# 2014_CANSAT_Power_Supply.net
KiCad netlist of a schematic drawn in EAGLE
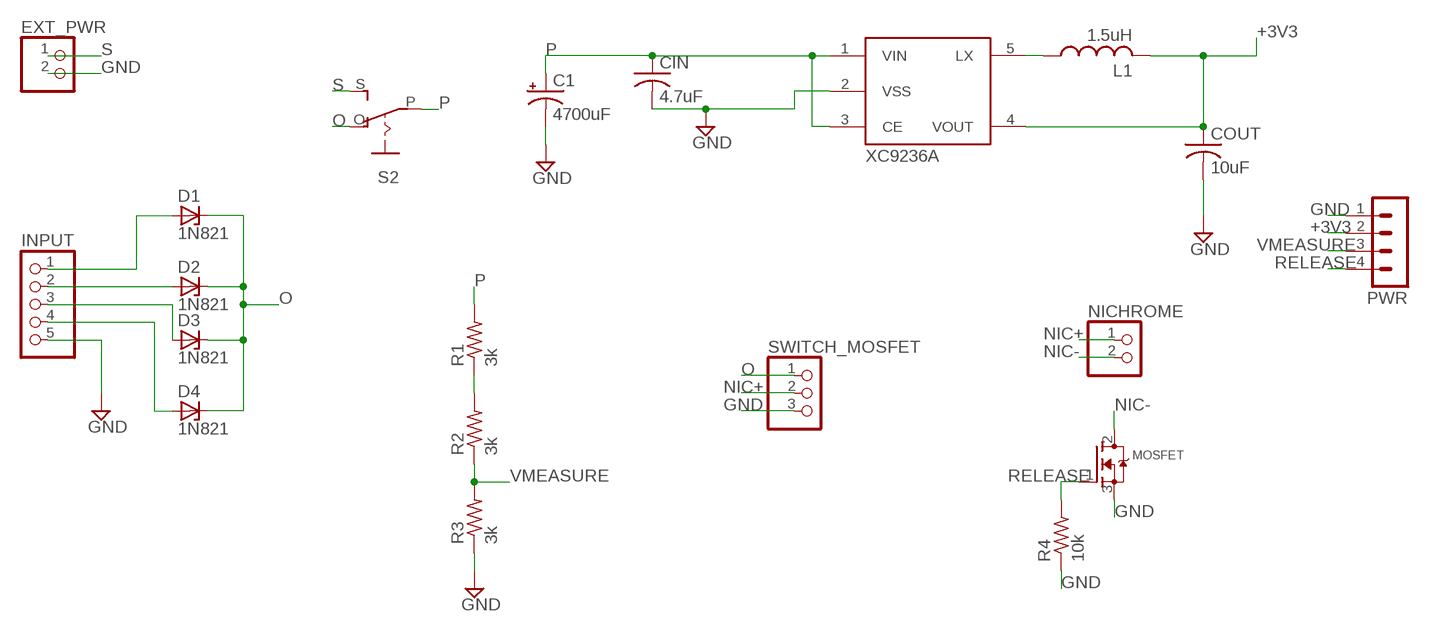
[diagram p0: schematic, sheet 1]

(export (version "E")
  (design (tool "Eeschema 10.0.6"))
  (components
    (comp (ref "C1")
      (value "4700uF")
      (footprint "eagle-import:E5-5")
      (libsource (lib "eagle-import") (part "CPOL-USE5-5"))
    )
    (comp (ref "CIN")
      (value "4.7uF")
      (footprint "eagle-import:C050-024X044")
      (libsource (lib "eagle-import") (part "C-US050-024X044"))
    )
    (comp (ref "COUT")
      (value "10uF")
      (footprint "eagle-import:C050-024X044")
      (libsource (lib "eagle-import") (part "C-US050-024X044"))
    )
    (comp (ref "D1")
      (value "1N821")
      (footprint "eagle-import:DO35Z10")
      (libsource (lib "eagle-import") (part "1N821"))
    )
    (comp (ref "D2")
      (value "1N821")
      (footprint "eagle-import:DO35Z10")
      (libsource (lib "eagle-import") (part "1N821"))
    )
    (comp (ref "D3")
      (value "1N821")
      (footprint "eagle-import:DO35Z10")
      (libsource (lib "eagle-import") (part "1N821"))
    )
    (comp (ref "D4")
      (value "1N821")
      (footprint "eagle-import:DO35Z10")
      (libsource (lib "eagle-import") (part "1N821"))
    )
    (comp (ref "EXT_PWR")
      (value "PINHD-1X2")
      (footprint "eagle-import:1X02")
      (libsource (lib "eagle-import") (part "PINHD-1X2"))
    )
    (comp (ref "INPUT")
      (value "PINHD-1X5")
      (footprint "eagle-import:1X05")
      (libsource (lib "eagle-import") (part "PINHD-1X5"))
    )
    (comp (ref "L1")
      (value "1.5uH")
      (footprint "eagle-import:6000-XXXX-RC")
      (libsource (lib "eagle-import") (part "L-US6000-XXX-RC"))
    )
    (comp (ref "MOSFET")
      (value "MOSFET-NGDS_TO220V")
      (footprint "eagle-import:TO220V")
      (libsource (lib "eagle-import") (part "MOSFET-NGDS_TO220V"))
    )
    (comp (ref "NICHROME")
      (value "PINHD-1X2")
      (footprint "eagle-import:1X02")
      (libsource (lib "eagle-import") (part "PINHD-1X2"))
    )
    (comp (ref "PWR")
      (value "MA04-1")
      (footprint "eagle-import:MA04-1")
      (libsource (lib "eagle-import") (part "MA04-1"))
    )
    (comp (ref "R1")
      (value "3k")
      (footprint "eagle-import:0309_10")
      (libsource (lib "eagle-import") (part "R-US_0309/10"))
    )
    (comp (ref "R2")
      (value "3k")
      (footprint "eagle-import:0309_10")
      (libsource (lib "eagle-import") (part "R-US_0309/10"))
    )
    (comp (ref "R3")
      (value "3k")
      (footprint "eagle-import:0309_10")
      (libsource (lib "eagle-import") (part "R-US_0309/10"))
    )
    (comp (ref "R4")
      (value "10k")
      (footprint "eagle-import:0309_10")
      (libsource (lib "eagle-import") (part "R-US_0309/10"))
    )
    (comp (ref "S2")
      (value "EG1218S")
      (footprint "eagle-import:EG1218")
      (libsource (lib "eagle-import") (part "EG1218S"))
    )
    (comp (ref "SWITCH_MOSFET")
      (value "PINHD-1X3")
      (footprint "eagle-import:1X03")
      (libsource (lib "eagle-import") (part "PINHD-1X3"))
    )
    (comp (ref "XC9236A")
      (value "MCP73811/2")
      (footprint "eagle-import:SOT23-5L")
      (libsource (lib "eagle-import") (part "MCP73811/2"))
    )
  )
  (nets
    (net (code "1") (name "/+3V3") (class "Default")
      (node (ref "COUT") (pin "1") (pinfunction "1_1") (pintype "passive"))
      (node (ref "L1") (pin "2") (pinfunction "2_2") (pintype "passive"))
      (node (ref "PWR") (pin "2") (pinfunction "2_2") (pintype "passive"))
      (node (ref "XC9236A") (pin "4") (pinfunction "VOUT_4") (pintype "power_in"))
    )
    (net (code "2") (name "/NIC+") (class "Default")
      (node (ref "NICHROME") (pin "1") (pinfunction "1_1") (pintype "passive"))
      (node (ref "SWITCH_MOSFET") (pin "2") (pinfunction "2_2") (pintype "passive"))
    )
    (net (code "3") (name "/NIC-") (class "Default")
      (node (ref "MOSFET") (pin "2") (pinfunction "D_2") (pintype "bidirectional"))
      (node (ref "NICHROME") (pin "2") (pinfunction "2_2") (pintype "passive"))
    )
    (net (code "4") (name "/O") (class "Default")
      (node (ref "D1") (pin "C") (pinfunction "C_C") (pintype "passive"))
      (node (ref "D2") (pin "C") (pinfunction "C_C") (pintype "passive"))
      (node (ref "D3") (pin "C") (pinfunction "C_C") (pintype "passive"))
      (node (ref "D4") (pin "C") (pinfunction "C_C") (pintype "passive"))
      (node (ref "S2") (pin "O") (pinfunction "O_O") (pintype "passive"))
      (node (ref "SWITCH_MOSFET") (pin "1") (pinfunction "1_1") (pintype "passive"))
    )
    (net (code "5") (name "/P") (class "Default")
      (node (ref "C1") (pin "+") (pinfunction "+_+") (pintype "passive"))
      (node (ref "CIN") (pin "1") (pinfunction "1_1") (pintype "passive"))
      (node (ref "R1") (pin "2") (pinfunction "2_2") (pintype "passive"))
      (node (ref "S2") (pin "P") (pinfunction "P_P") (pintype "passive"))
      (node (ref "XC9236A") (pin "1") (pinfunction "VIN_1") (pintype "input"))
      (node (ref "XC9236A") (pin "3") (pinfunction "CE_3") (pintype "bidirectional"))
    )
    (net (code "6") (name "/RELEASE") (class "Default")
      (node (ref "MOSFET") (pin "1") (pinfunction "G_1") (pintype "bidirectional"))
      (node (ref "PWR") (pin "4") (pinfunction "4_4") (pintype "passive"))
      (node (ref "R4") (pin "2") (pinfunction "2_2") (pintype "passive"))
    )
    (net (code "7") (name "/S") (class "Default")
      (node (ref "EXT_PWR") (pin "1") (pinfunction "1_1") (pintype "passive"))
      (node (ref "S2") (pin "S") (pinfunction "S_S") (pintype "passive"))
    )
    (net (code "8") (name "/VMEASURE") (class "Default")
      (node (ref "PWR") (pin "3") (pinfunction "3_3") (pintype "passive"))
      (node (ref "R2") (pin "1") (pinfunction "1_1") (pintype "passive"))
      (node (ref "R3") (pin "2") (pinfunction "2_2") (pintype "passive"))
    )
    (net (code "9") (name "GND") (class "Default")
      (node (ref "C1") (pin "-") (pinfunction "-_-") (pintype "passive"))
      (node (ref "CIN") (pin "2") (pinfunction "2_2") (pintype "passive"))
      (node (ref "COUT") (pin "2") (pinfunction "2_2") (pintype "passive"))
      (node (ref "EXT_PWR") (pin "2") (pinfunction "2_2") (pintype "passive"))
      (node (ref "INPUT") (pin "5") (pinfunction "5_5") (pintype "passive"))
      (node (ref "MOSFET") (pin "3") (pinfunction "S_3") (pintype "bidirectional"))
      (node (ref "PWR") (pin "1") (pinfunction "1_1") (pintype "passive"))
      (node (ref "R3") (pin "1") (pinfunction "1_1") (pintype "passive"))
      (node (ref "R4") (pin "1") (pinfunction "1_1") (pintype "passive"))
      (node (ref "SWITCH_MOSFET") (pin "3") (pinfunction "3_3") (pintype "passive"))
      (node (ref "XC9236A") (pin "2") (pinfunction "VSS_2") (pintype "power_in"))
    )
    (net (code "10") (name "Net-(D1-PadA)") (class "Default")
      (node (ref "D1") (pin "A") (pinfunction "A_A") (pintype "passive"))
      (node (ref "INPUT") (pin "1") (pinfunction "1_1") (pintype "passive"))
    )
    (net (code "11") (name "Net-(D2-PadA)") (class "Default")
      (node (ref "D2") (pin "A") (pinfunction "A_A") (pintype "passive"))
      (node (ref "INPUT") (pin "2") (pinfunction "2_2") (pintype "passive"))
    )
    (net (code "12") (name "Net-(D3-PadA)") (class "Default")
      (node (ref "D3") (pin "A") (pinfunction "A_A") (pintype "passive"))
      (node (ref "INPUT") (pin "3") (pinfunction "3_3") (pintype "passive"))
    )
    (net (code "13") (name "Net-(D4-PadA)") (class "Default")
      (node (ref "D4") (pin "A") (pinfunction "A_A") (pintype "passive"))
      (node (ref "INPUT") (pin "4") (pinfunction "4_4") (pintype "passive"))
    )
    (net (code "14") (name "Net-(R1-Pad1)") (class "Default")
      (node (ref "R1") (pin "1") (pinfunction "1_1") (pintype "passive"))
      (node (ref "R2") (pin "2") (pinfunction "2_2") (pintype "passive"))
    )
    (net (code "15") (name "Net-(XC9236A-LX)") (class "Default")
      (node (ref "L1") (pin "1") (pinfunction "1_1") (pintype "passive"))
      (node (ref "XC9236A") (pin "5") (pinfunction "LX_5") (pintype "input"))
    )
  )
)
